# Power.net
KiCad netlist of a schematic drawn in Altium Designer
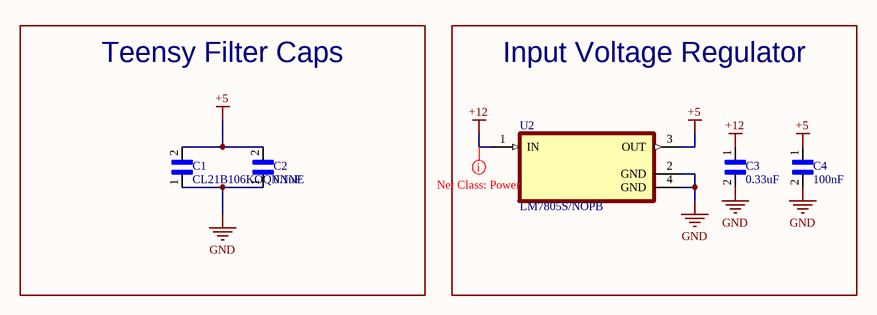
[diagram p0: Power.SchDoc]

(export (version "E")
  (design (tool "Eeschema 10.0.6"))
  (components
    (comp (ref "C1")
      (value "CL21B106KOQNNNE")
      (footprint "CL21B106KOQNNNE:CAPC2012X140N")
      (description "Cap Ceramic 10uF 16V X7R 10% Pad SMD 0805 125C T/R")
      (fields (field (name "MF") "{'manufacturer': u'Samsung'}"))
      (libsource (lib "*") (part "CL21B106KOQNNNE"))
    )
    (comp (ref "C2")
      (value "0.1uF")
      (footprint "08055G104ZAT1A:CAPC2012X140N")
      (fields (field (name "MP") "08055G104ZAT1A") (field (name "MF") "{'manufacturer': u'AVX'}"))
      (libsource (lib "*") (part "08055G104ZAT1A"))
    )
    (comp (ref "C3")
      (value "0.33uF")
      (footprint "C0805C334J5RECAUTO:CAPC2012X100N")
      (fields (field (name "MF") "{'manufacturer': u'KEMET'}") (field (name "MP") "C0805C334J5RECAUTO"))
      (libsource (lib "*") (part "C0805C334J5RECAUTO"))
    )
    (comp (ref "C4")
      (value "100nF")
      (footprint "08055G104ZAT1A:CAPC2012X140N")
      (fields (field (name "MP") "08055G104ZAT1A") (field (name "MF") "{'manufacturer': u'AVX'}"))
      (libsource (lib "08055G104ZAT1A") (part "08055G104ZAT1A"))
    )
    (comp (ref "U2")
      (value "LM7805S/NOPB")
      (footprint "LM7805S_NOPB:TO254P1524X483-4N")
      (fields (field (name "MF") "{'manufacturer': u'Texas Instruments'}"))
      (libsource (lib "*") (part "LM7805S/NOPB"))
    )
  )
  (nets
    (net (code "1") (name "+5") (class "Default")
      (node (ref "C1") (pin "2") (pinfunction "2_2") (pintype "passive"))
      (node (ref "C2") (pin "2") (pinfunction "2_2") (pintype "passive"))
      (node (ref "C4") (pin "1") (pinfunction "1_1") (pintype "passive"))
      (node (ref "U2") (pin "3") (pinfunction "OUT_3") (pintype "output"))
    )
    (net (code "2") (name "+12") (class "Default")
      (node (ref "C3") (pin "1") (pinfunction "1_1") (pintype "passive"))
      (node (ref "U2") (pin "1") (pinfunction "IN_1") (pintype "input"))
    )
    (net (code "3") (name "GND") (class "Default")
      (node (ref "C1") (pin "1") (pinfunction "1_1") (pintype "passive"))
      (node (ref "C2") (pin "1") (pinfunction "1_1") (pintype "passive"))
      (node (ref "C3") (pin "2") (pinfunction "2_2") (pintype "passive"))
      (node (ref "C4") (pin "2") (pinfunction "2_2") (pintype "passive"))
      (node (ref "U2") (pin "2") (pinfunction "GND_2") (pintype "power_in"))
      (node (ref "U2") (pin "4") (pinfunction "GND_4") (pintype "power_in"))
    )
  )
)
